# Adafruit_STEMMA_QT_Booster_Breakout.net
KiCad netlist of a schematic drawn in EAGLE
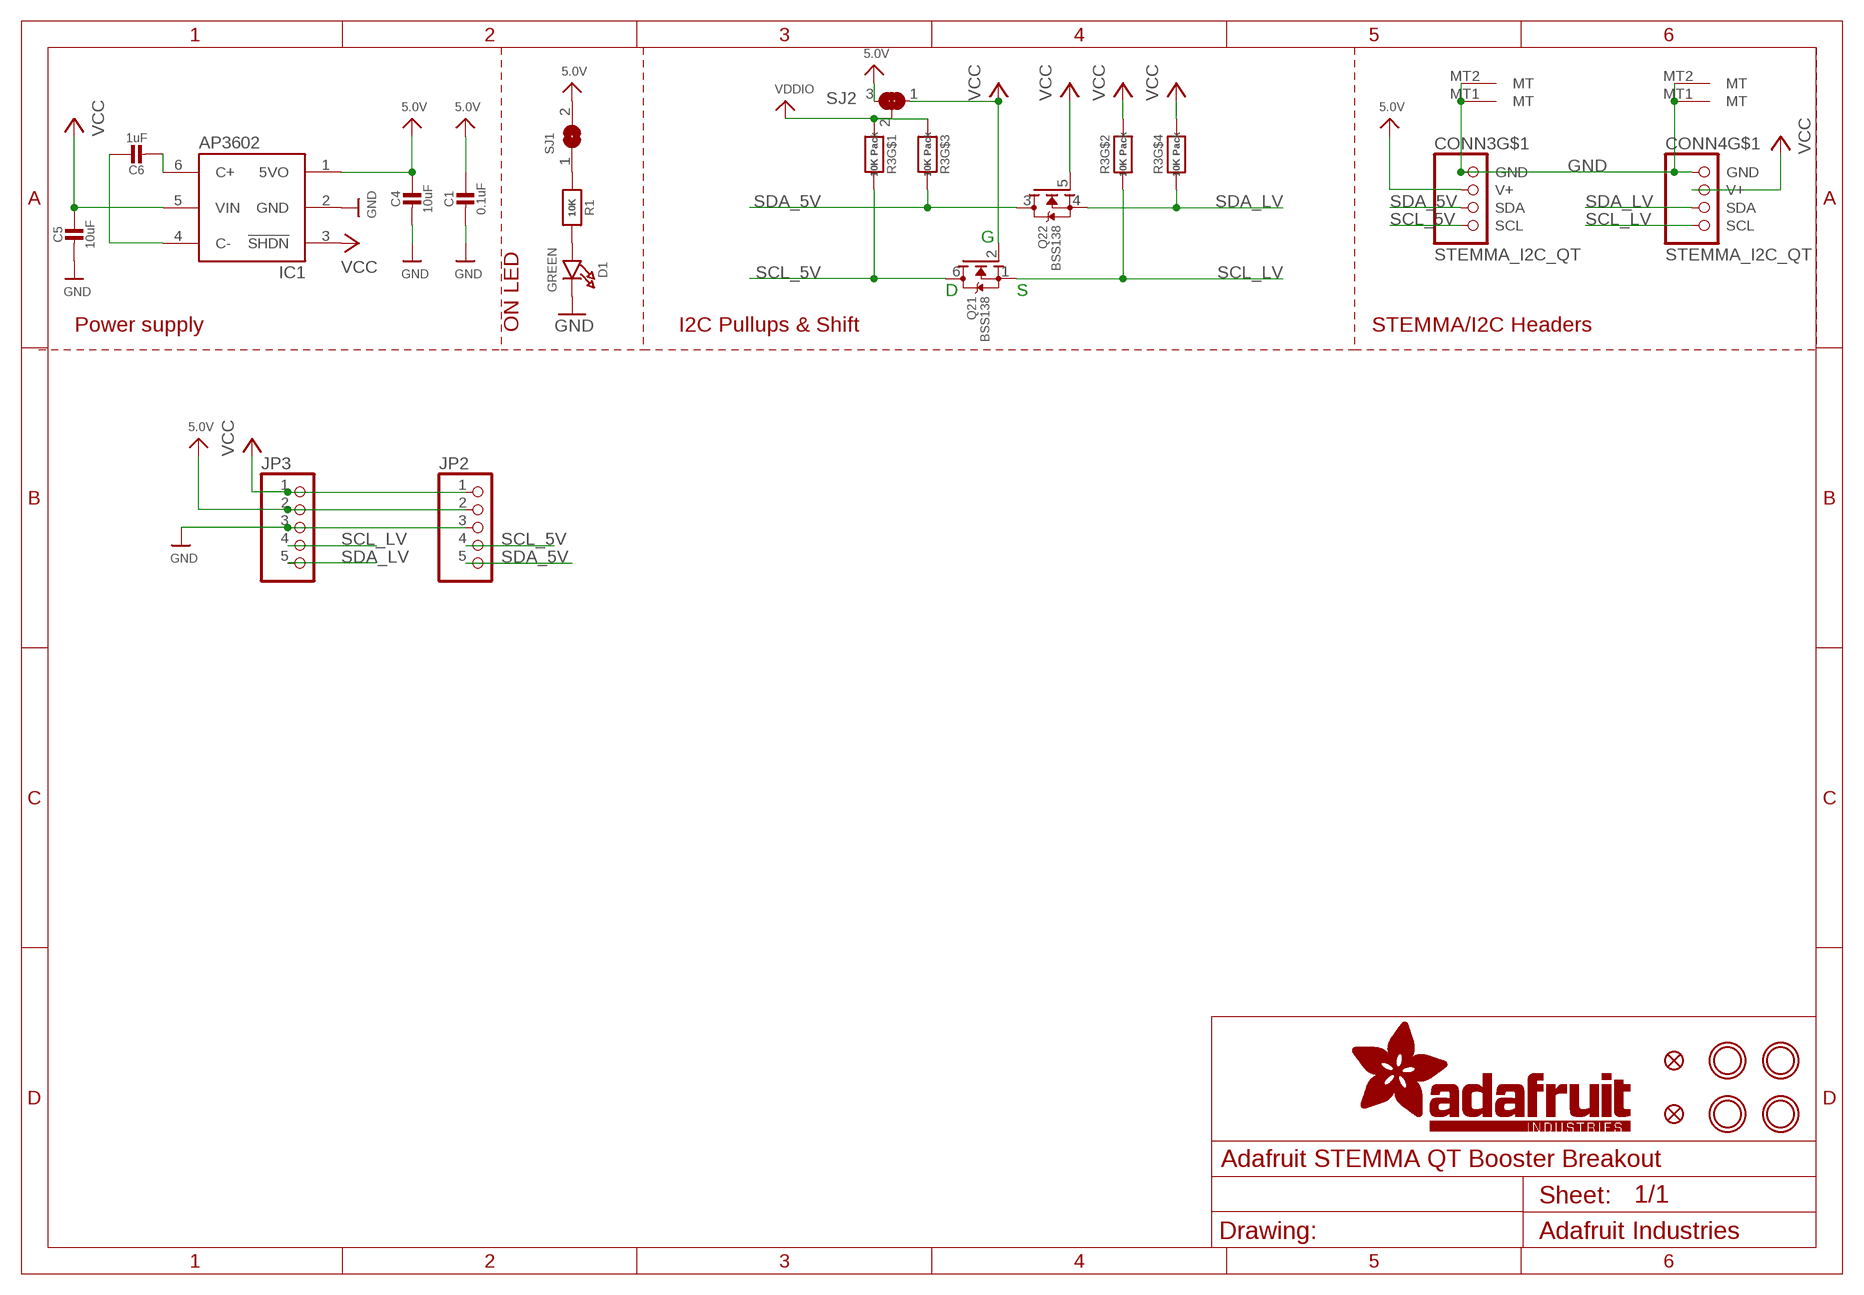
[diagram p0: schematic, sheet 1]

(export (version "E")
  (design (tool "Eeschema 10.0.6"))
  (components
    (comp (ref "C1")
      (value "0.1uF")
      (footprint "eagle-import:0603-NO")
      (libsource (lib "eagle-import") (part "CAP_CERAMIC0603_NO"))
    )
    (comp (ref "C4")
      (value "10uF")
      (footprint "eagle-import:0805-NO")
      (libsource (lib "eagle-import") (part "CAP_CERAMIC0805-NOOUTLINE"))
    )
    (comp (ref "C5")
      (value "10uF")
      (footprint "eagle-import:0805-NO")
      (libsource (lib "eagle-import") (part "CAP_CERAMIC0805-NOOUTLINE"))
    )
    (comp (ref "C6")
      (value "1uF")
      (footprint "eagle-import:0805-NO")
      (libsource (lib "eagle-import") (part "CAP_CERAMIC0805-NOOUTLINE"))
    )
    (comp (ref "CONN3")
      (value "STEMMA_I2C_QT")
      (footprint "eagle-import:JST_SH4")
      (libsource (lib "eagle-import") (part "STEMMA_I2C_QT"))
    )
    (comp (ref "CONN4")
      (value "STEMMA_I2C_QT")
      (footprint "eagle-import:JST_SH4")
      (libsource (lib "eagle-import") (part "STEMMA_I2C_QT"))
    )
    (comp (ref "D1")
      (value "GREEN")
      (footprint "eagle-import:CHIPLED_0603_NOOUTLINE")
      (libsource (lib "eagle-import") (part "LED0603_NOOUTLINE"))
    )
    (comp (ref "FID3")
      (value "FIDUCIAL_1MM")
      (footprint "eagle-import:FIDUCIAL_1MM")
      (libsource (lib "eagle-import") (part "FIDUCIAL_1MM"))
    )
    (comp (ref "FID4")
      (value "FIDUCIAL_1MM")
      (footprint "eagle-import:FIDUCIAL_1MM")
      (libsource (lib "eagle-import") (part "FIDUCIAL_1MM"))
    )
    (comp (ref "IC1")
      (value "AP3602/RT9361")
      (footprint "eagle-import:SOT23-6")
      (libsource (lib "eagle-import") (part "AP3602"))
    )
    (comp (ref "JP2")
      (value "HEADER-1X576MIL")
      (footprint "eagle-import:1X05_ROUND_76")
      (libsource (lib "eagle-import") (part "HEADER-1X576MIL"))
    )
    (comp (ref "JP3")
      (value "HEADER-1X576MIL")
      (footprint "eagle-import:1X05_ROUND_76")
      (libsource (lib "eagle-import") (part "HEADER-1X576MIL"))
    )
    (comp (ref "Q2")
      (value "BSS138")
      (footprint "eagle-import:SOT363")
      (libsource (lib "eagle-import") (part "MOSFET-N_DUAL"))
    )
    (comp (ref "R1")
      (value "10K")
      (footprint "eagle-import:0603-NO")
      (libsource (lib "eagle-import") (part "RESISTOR_0603_NOOUT"))
    )
    (comp (ref "R3")
      (value "10K Pack")
      (footprint "eagle-import:RESPACK_4X0603")
      (libsource (lib "eagle-import") (part "RESISTOR_4PACK"))
    )
    (comp (ref "SJ1")
      (value "SOLDERJUMPERCLOSED")
      (footprint "eagle-import:SOLDERJUMPER_CLOSEDWIRE")
      (libsource (lib "eagle-import") (part "SOLDERJUMPERCLOSED"))
    )
    (comp (ref "SJ2")
      (value "SOLDERJUMPER_2WAY")
      (footprint "eagle-import:SOLDERJUMPER_2WAY_OPEN_NOPASTE")
      (libsource (lib "eagle-import") (part "SOLDERJUMPER_2WAY"))
    )
    (comp (ref "U$1")
      (value "MOUNTINGHOLE2.5")
      (footprint "eagle-import:MOUNTINGHOLE_2.5_PLATED")
      (libsource (lib "eagle-import") (part "MOUNTINGHOLE2.5"))
    )
    (comp (ref "U$17")
      (value "MOUNTINGHOLE2.5")
      (footprint "eagle-import:MOUNTINGHOLE_2.5_PLATED")
      (libsource (lib "eagle-import") (part "MOUNTINGHOLE2.5"))
    )
    (comp (ref "U$19")
      (value "MOUNTINGHOLE2.5")
      (footprint "eagle-import:MOUNTINGHOLE_2.5_PLATED")
      (libsource (lib "eagle-import") (part "MOUNTINGHOLE2.5"))
    )
    (comp (ref "U$21")
      (value "MOUNTINGHOLE2.5")
      (footprint "eagle-import:MOUNTINGHOLE_2.5_PLATED")
      (libsource (lib "eagle-import") (part "MOUNTINGHOLE2.5"))
    )
  )
  (nets
    (net (code "1") (name "/SCL_5V") (class "Default")
      (node (ref "CONN3") (pin "4") (pinfunction "SCL_4") (pintype "passive"))
      (node (ref "JP2") (pin "4") (pinfunction "4_4") (pintype "passive"))
      (node (ref "Q2") (pin "6") (pinfunction "D_6") (pintype "bidirectional"))
      (node (ref "R3") (pin "8") (pinfunction "2_8") (pintype "passive"))
    )
    (net (code "2") (name "/SCL_LV") (class "Default")
      (node (ref "CONN4") (pin "4") (pinfunction "SCL_4") (pintype "passive"))
      (node (ref "JP3") (pin "4") (pinfunction "4_4") (pintype "passive"))
      (node (ref "Q2") (pin "1") (pinfunction "S_1") (pintype "bidirectional"))
      (node (ref "R3") (pin "7") (pinfunction "2_7") (pintype "passive"))
    )
    (net (code "3") (name "/SDA_5V") (class "Default")
      (node (ref "CONN3") (pin "3") (pinfunction "SDA_3") (pintype "passive"))
      (node (ref "JP2") (pin "5") (pinfunction "5_5") (pintype "passive"))
      (node (ref "Q2") (pin "3") (pinfunction "D_3") (pintype "bidirectional"))
      (node (ref "R3") (pin "6") (pinfunction "2_6") (pintype "passive"))
    )
    (net (code "4") (name "/SDA_LV") (class "Default")
      (node (ref "CONN4") (pin "3") (pinfunction "SDA_3") (pintype "passive"))
      (node (ref "JP3") (pin "5") (pinfunction "5_5") (pintype "passive"))
      (node (ref "Q2") (pin "4") (pinfunction "S_4") (pintype "bidirectional"))
      (node (ref "R3") (pin "5") (pinfunction "2_5") (pintype "passive"))
    )
    (net (code "5") (name "5.0V") (class "Default")
      (node (ref "C1") (pin "1") (pinfunction "1_1") (pintype "passive"))
      (node (ref "C4") (pin "1") (pinfunction "1_1") (pintype "passive"))
      (node (ref "CONN3") (pin "2") (pinfunction "V+_2") (pintype "passive"))
      (node (ref "IC1") (pin "1") (pinfunction "5VO_1") (pintype "power_in"))
      (node (ref "JP2") (pin "2") (pinfunction "2_2") (pintype "passive"))
      (node (ref "JP3") (pin "2") (pinfunction "2_2") (pintype "passive"))
      (node (ref "SJ1") (pin "2") (pinfunction "2_2") (pintype "passive"))
      (node (ref "SJ2") (pin "3") (pinfunction "3_3") (pintype "passive"))
    )
    (net (code "6") (name "GND") (class "Default")
      (node (ref "C1") (pin "2") (pinfunction "2_2") (pintype "passive"))
      (node (ref "C4") (pin "2") (pinfunction "2_2") (pintype "passive"))
      (node (ref "C5") (pin "2") (pinfunction "2_2") (pintype "passive"))
      (node (ref "CONN3") (pin "1") (pinfunction "GND_1") (pintype "passive"))
      (node (ref "CONN3") (pin "MT1") (pinfunction "MT_MT1") (pintype "bidirectional"))
      (node (ref "CONN3") (pin "MT2") (pinfunction "MT_MT2") (pintype "bidirectional"))
      (node (ref "CONN4") (pin "1") (pinfunction "GND_1") (pintype "passive"))
      (node (ref "CONN4") (pin "MT1") (pinfunction "MT_MT1") (pintype "bidirectional"))
      (node (ref "CONN4") (pin "MT2") (pinfunction "MT_MT2") (pintype "bidirectional"))
      (node (ref "D1") (pin "C") (pinfunction "C_C") (pintype "passive"))
      (node (ref "IC1") (pin "2") (pinfunction "GND_2") (pintype "power_in"))
      (node (ref "JP2") (pin "3") (pinfunction "3_3") (pintype "passive"))
      (node (ref "JP3") (pin "3") (pinfunction "3_3") (pintype "passive"))
    )
    (net (code "7") (name "Net-(D1-PadA)") (class "Default")
      (node (ref "D1") (pin "A") (pinfunction "A_A") (pintype "passive"))
      (node (ref "R1") (pin "2") (pinfunction "2_2") (pintype "passive"))
    )
    (net (code "8") (name "Net-(IC1-C+)") (class "Default")
      (node (ref "C6") (pin "2") (pinfunction "2_2") (pintype "passive"))
      (node (ref "IC1") (pin "6") (pinfunction "C+_6") (pintype "bidirectional"))
    )
    (net (code "9") (name "Net-(IC1-C-)") (class "Default")
      (node (ref "C6") (pin "1") (pinfunction "1_1") (pintype "passive"))
      (node (ref "IC1") (pin "4") (pinfunction "C-_4") (pintype "bidirectional"))
    )
    (net (code "10") (name "Net-(R1-Pad1)") (class "Default")
      (node (ref "R1") (pin "1") (pinfunction "1_1") (pintype "passive"))
      (node (ref "SJ1") (pin "1") (pinfunction "1_1") (pintype "passive"))
    )
    (net (code "11") (name "VCC") (class "Default")
      (node (ref "C5") (pin "1") (pinfunction "1_1") (pintype "passive"))
      (node (ref "CONN4") (pin "2") (pinfunction "V+_2") (pintype "passive"))
      (node (ref "IC1") (pin "3") (pinfunction "~{SHDN}_3") (pintype "input"))
      (node (ref "IC1") (pin "5") (pinfunction "VIN_5") (pintype "power_in"))
      (node (ref "JP2") (pin "1") (pinfunction "1_1") (pintype "passive"))
      (node (ref "JP3") (pin "1") (pinfunction "1_1") (pintype "passive"))
      (node (ref "Q2") (pin "2") (pinfunction "G_2") (pintype "bidirectional"))
      (node (ref "Q2") (pin "5") (pinfunction "G_5") (pintype "bidirectional"))
      (node (ref "R3") (pin "2") (pinfunction "1_2") (pintype "passive"))
      (node (ref "R3") (pin "4") (pinfunction "1_4") (pintype "passive"))
      (node (ref "SJ2") (pin "1") (pinfunction "1_1") (pintype "passive"))
    )
    (net (code "12") (name "VDDIO") (class "Default")
      (node (ref "R3") (pin "1") (pinfunction "1_1") (pintype "passive"))
      (node (ref "R3") (pin "3") (pinfunction "1_3") (pintype "passive"))
      (node (ref "SJ2") (pin "2") (pinfunction "2_2") (pintype "passive"))
    )
  )
)
